# isl-test.net
KiCad netlist of a schematic drawn in EAGLE
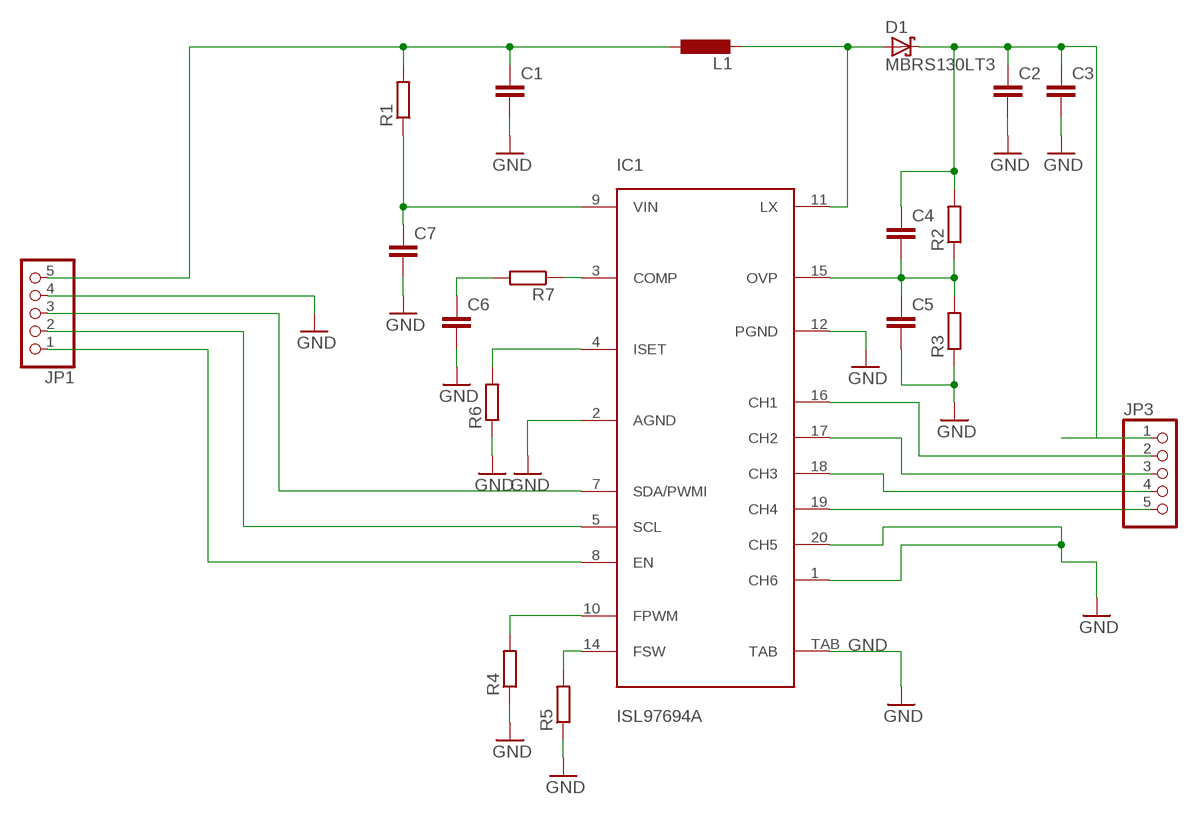
[diagram p0: schematic, sheet 1]

(export (version "E")
  (design (tool "Eeschema 10.0.6"))
  (components
    (comp (ref "C1")
      (value "C-EUC0805")
      (footprint "eagle-import:C0805")
      (libsource (lib "eagle-import") (part "C-EUC0805"))
    )
    (comp (ref "C2")
      (value "C-EUC0805")
      (footprint "eagle-import:C0805")
      (libsource (lib "eagle-import") (part "C-EUC0805"))
    )
    (comp (ref "C3")
      (value "C-EUC0805")
      (footprint "eagle-import:C0805")
      (libsource (lib "eagle-import") (part "C-EUC0805"))
    )
    (comp (ref "C4")
      (value "C-EUC0603")
      (footprint "eagle-import:C0603")
      (libsource (lib "eagle-import") (part "C-EUC0603"))
    )
    (comp (ref "C5")
      (value "C-EUC0603")
      (footprint "eagle-import:C0603")
      (libsource (lib "eagle-import") (part "C-EUC0603"))
    )
    (comp (ref "C6")
      (value "C-EUC0603")
      (footprint "eagle-import:C0603")
      (libsource (lib "eagle-import") (part "C-EUC0603"))
    )
    (comp (ref "C7")
      (value "C-EUC0603")
      (footprint "eagle-import:C0603")
      (libsource (lib "eagle-import") (part "C-EUC0603"))
    )
    (comp (ref "D1")
      (value "MBRS130LT3")
      (footprint "eagle-import:SMB")
      (libsource (lib "eagle-import") (part "MBRS130LT3"))
    )
    (comp (ref "IC1")
      (value "ISL97694A")
      (footprint "eagle-import:TQFN-20")
      (libsource (lib "eagle-import") (part "ISL97694A"))
    )
    (comp (ref "JP1")
      (value "PINHD-1X5")
      (footprint "eagle-import:1X05")
      (libsource (lib "eagle-import") (part "PINHD-1X5"))
    )
    (comp (ref "JP3")
      (value "PINHD-1X5")
      (footprint "eagle-import:1X05")
      (libsource (lib "eagle-import") (part "PINHD-1X5"))
    )
    (comp (ref "L1")
      (value "L-EUL1812")
      (footprint "eagle-import:L1812")
      (libsource (lib "eagle-import") (part "L-EUL1812"))
    )
    (comp (ref "R1")
      (value "R-EU_R0603")
      (footprint "eagle-import:R0603")
      (libsource (lib "eagle-import") (part "R-EU_R0603"))
    )
    (comp (ref "R2")
      (value "R-EU_R0603")
      (footprint "eagle-import:R0603")
      (libsource (lib "eagle-import") (part "R-EU_R0603"))
    )
    (comp (ref "R3")
      (value "R-EU_R0603")
      (footprint "eagle-import:R0603")
      (libsource (lib "eagle-import") (part "R-EU_R0603"))
    )
    (comp (ref "R4")
      (value "R-EU_R0603")
      (footprint "eagle-import:R0603")
      (libsource (lib "eagle-import") (part "R-EU_R0603"))
    )
    (comp (ref "R5")
      (value "R-EU_R0603")
      (footprint "eagle-import:R0603")
      (libsource (lib "eagle-import") (part "R-EU_R0603"))
    )
    (comp (ref "R6")
      (value "R-EU_R0603")
      (footprint "eagle-import:R0603")
      (libsource (lib "eagle-import") (part "R-EU_R0603"))
    )
    (comp (ref "R7")
      (value "R-EU_R0603")
      (footprint "eagle-import:R0603")
      (libsource (lib "eagle-import") (part "R-EU_R0603"))
    )
  )
  (nets
    (net (code "1") (name "GND") (class "Default")
      (node (ref "C1") (pin "2") (pinfunction "2_2") (pintype "passive"))
      (node (ref "C2") (pin "2") (pinfunction "2_2") (pintype "passive"))
      (node (ref "C3") (pin "2") (pinfunction "2_2") (pintype "passive"))
      (node (ref "C5") (pin "2") (pinfunction "2_2") (pintype "passive"))
      (node (ref "C6") (pin "2") (pinfunction "2_2") (pintype "passive"))
      (node (ref "C7") (pin "2") (pinfunction "2_2") (pintype "passive"))
      (node (ref "IC1") (pin "1") (pinfunction "CH6_1") (pintype "input"))
      (node (ref "IC1") (pin "12") (pinfunction "PGND_12") (pintype "power_in"))
      (node (ref "IC1") (pin "2") (pinfunction "AGND_2") (pintype "power_in"))
      (node (ref "IC1") (pin "20") (pinfunction "CH5_20") (pintype "input"))
      (node (ref "IC1") (pin "TAB") (pinfunction "TAB_TAB") (pintype "power_in"))
      (node (ref "JP1") (pin "4") (pinfunction "4_4") (pintype "passive"))
      (node (ref "R3") (pin "1") (pinfunction "1_1") (pintype "passive"))
      (node (ref "R4") (pin "1") (pinfunction "1_1") (pintype "passive"))
      (node (ref "R5") (pin "1") (pinfunction "1_1") (pintype "passive"))
      (node (ref "R6") (pin "1") (pinfunction "1_1") (pintype "passive"))
    )
    (net (code "2") (name "Net-(C1-Pad1)") (class "Default")
      (node (ref "C1") (pin "1") (pinfunction "1_1") (pintype "passive"))
      (node (ref "JP1") (pin "5") (pinfunction "5_5") (pintype "passive"))
      (node (ref "L1") (pin "1") (pinfunction "1_1") (pintype "passive"))
      (node (ref "R1") (pin "2") (pinfunction "2_2") (pintype "passive"))
    )
    (net (code "3") (name "Net-(C2-Pad1)") (class "Default")
      (node (ref "C2") (pin "1") (pinfunction "1_1") (pintype "passive"))
      (node (ref "C3") (pin "1") (pinfunction "1_1") (pintype "passive"))
      (node (ref "C4") (pin "1") (pinfunction "1_1") (pintype "passive"))
      (node (ref "D1") (pin "C") (pinfunction "C_C") (pintype "passive"))
      (node (ref "JP3") (pin "1") (pinfunction "1_1") (pintype "passive"))
      (node (ref "R2") (pin "2") (pinfunction "2_2") (pintype "passive"))
    )
    (net (code "4") (name "Net-(C6-Pad1)") (class "Default")
      (node (ref "C6") (pin "1") (pinfunction "1_1") (pintype "passive"))
      (node (ref "R7") (pin "2") (pinfunction "2_2") (pintype "passive"))
    )
    (net (code "5") (name "Net-(IC1-CH1)") (class "Default")
      (node (ref "IC1") (pin "16") (pinfunction "CH1_16") (pintype "input"))
      (node (ref "JP3") (pin "2") (pinfunction "2_2") (pintype "passive"))
    )
    (net (code "6") (name "Net-(IC1-CH2)") (class "Default")
      (node (ref "IC1") (pin "17") (pinfunction "CH2_17") (pintype "input"))
      (node (ref "JP3") (pin "3") (pinfunction "3_3") (pintype "passive"))
    )
    (net (code "7") (name "Net-(IC1-CH3)") (class "Default")
      (node (ref "IC1") (pin "18") (pinfunction "CH3_18") (pintype "input"))
      (node (ref "JP3") (pin "4") (pinfunction "4_4") (pintype "passive"))
    )
    (net (code "8") (name "Net-(IC1-CH4)") (class "Default")
      (node (ref "IC1") (pin "19") (pinfunction "CH4_19") (pintype "input"))
      (node (ref "JP3") (pin "5") (pinfunction "5_5") (pintype "passive"))
    )
    (net (code "9") (name "Net-(IC1-COMP)") (class "Default")
      (node (ref "IC1") (pin "3") (pinfunction "COMP_3") (pintype "bidirectional"))
      (node (ref "R7") (pin "1") (pinfunction "1_1") (pintype "passive"))
    )
    (net (code "10") (name "Net-(IC1-EN)") (class "Default")
      (node (ref "IC1") (pin "8") (pinfunction "EN_8") (pintype "input"))
      (node (ref "JP1") (pin "1") (pinfunction "1_1") (pintype "passive"))
    )
    (net (code "11") (name "Net-(IC1-FPWM)") (class "Default")
      (node (ref "IC1") (pin "10") (pinfunction "FPWM_10") (pintype "bidirectional"))
      (node (ref "R4") (pin "2") (pinfunction "2_2") (pintype "passive"))
    )
    (net (code "12") (name "Net-(IC1-FSW)") (class "Default")
      (node (ref "IC1") (pin "14") (pinfunction "FSW_14") (pintype "bidirectional"))
      (node (ref "R5") (pin "2") (pinfunction "2_2") (pintype "passive"))
    )
    (net (code "13") (name "Net-(IC1-ISET)") (class "Default")
      (node (ref "IC1") (pin "4") (pinfunction "ISET_4") (pintype "bidirectional"))
      (node (ref "R6") (pin "2") (pinfunction "2_2") (pintype "passive"))
    )
    (net (code "14") (name "Net-(IC1-LX)") (class "Default")
      (node (ref "D1") (pin "A") (pinfunction "A_A") (pintype "passive"))
      (node (ref "IC1") (pin "11") (pinfunction "LX_11") (pintype "power_in"))
      (node (ref "L1") (pin "2") (pinfunction "2_2") (pintype "passive"))
    )
    (net (code "15") (name "Net-(IC1-OVP)") (class "Default")
      (node (ref "C4") (pin "2") (pinfunction "2_2") (pintype "passive"))
      (node (ref "C5") (pin "1") (pinfunction "1_1") (pintype "passive"))
      (node (ref "IC1") (pin "15") (pinfunction "OVP_15") (pintype "bidirectional"))
      (node (ref "R2") (pin "1") (pinfunction "1_1") (pintype "passive"))
      (node (ref "R3") (pin "2") (pinfunction "2_2") (pintype "passive"))
    )
    (net (code "16") (name "Net-(IC1-SCL)") (class "Default")
      (node (ref "IC1") (pin "5") (pinfunction "SCL_5") (pintype "input"))
      (node (ref "JP1") (pin "2") (pinfunction "2_2") (pintype "passive"))
    )
    (net (code "17") (name "Net-(IC1-SDA{slash}PWMI)") (class "Default")
      (node (ref "IC1") (pin "7") (pinfunction "SDA/PWMI_7") (pintype "bidirectional"))
      (node (ref "JP1") (pin "3") (pinfunction "3_3") (pintype "passive"))
    )
    (net (code "18") (name "Net-(IC1-VIN)") (class "Default")
      (node (ref "C7") (pin "1") (pinfunction "1_1") (pintype "passive"))
      (node (ref "IC1") (pin "9") (pinfunction "VIN_9") (pintype "power_in"))
      (node (ref "R1") (pin "1") (pinfunction "1_1") (pintype "passive"))
    )
  )
)
